# schematic.net
KiCad netlist of a schematic drawn in EasyEDA
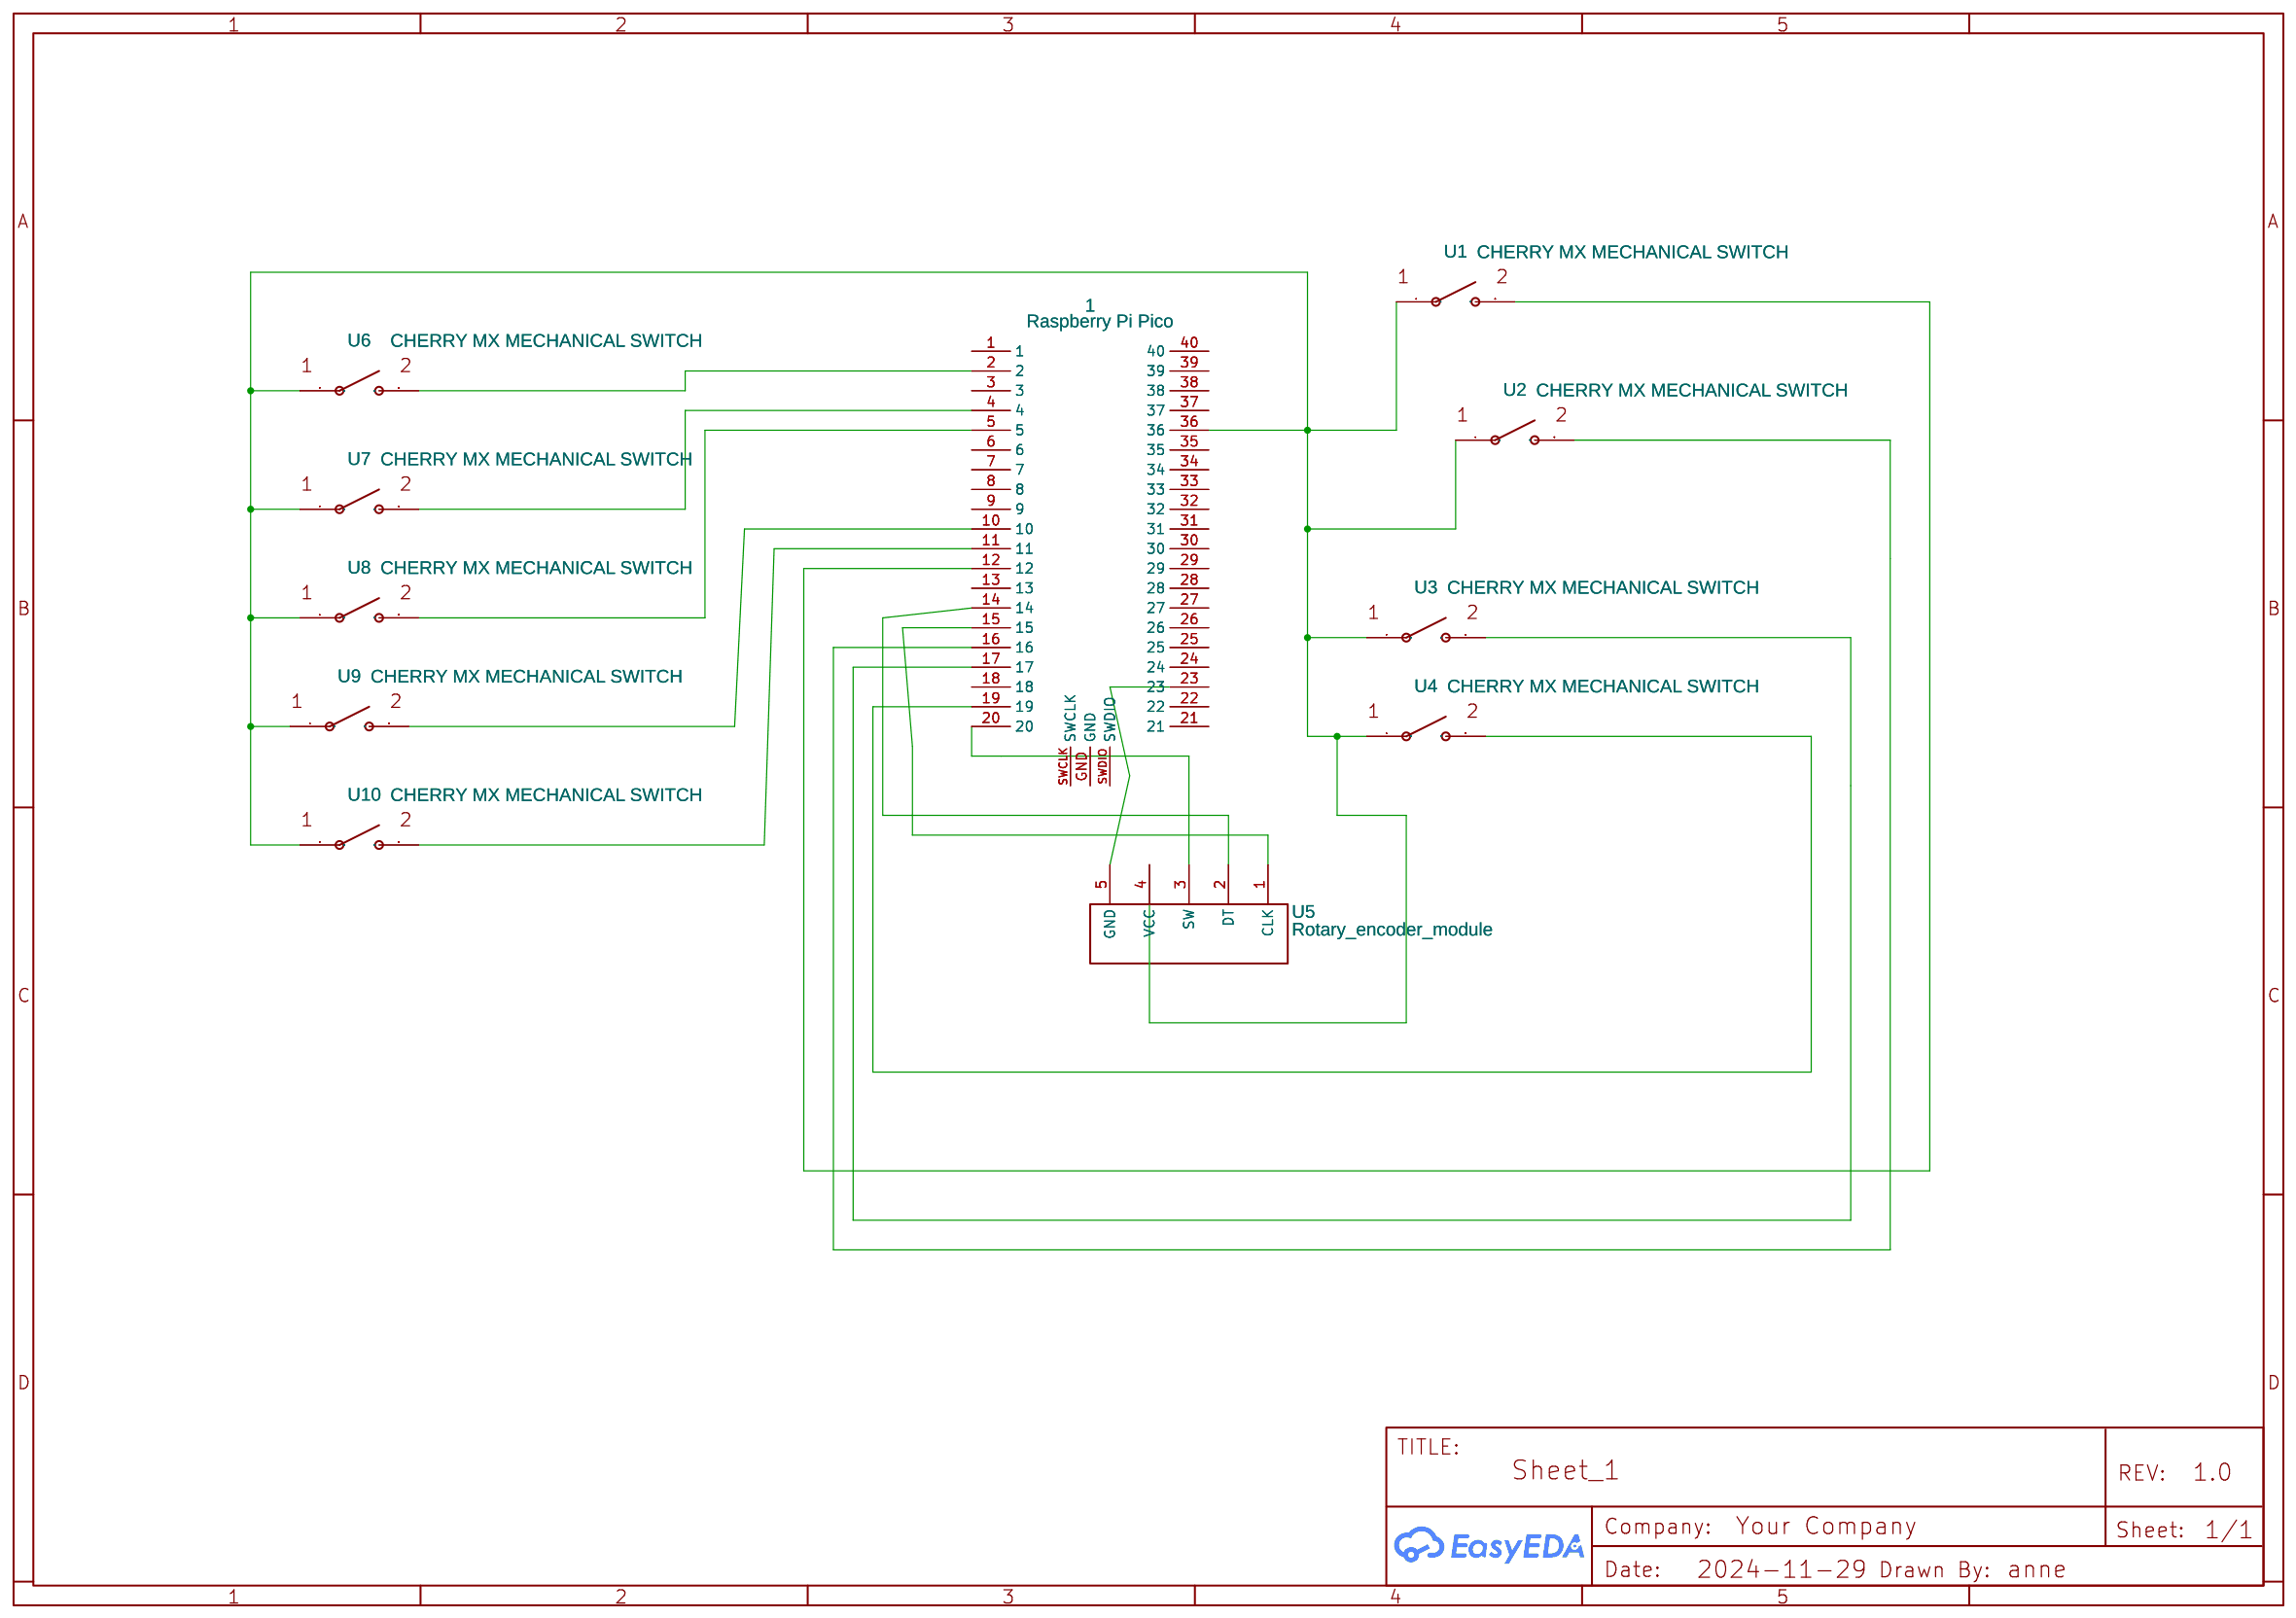
[diagram p0: schematic sheet]

(export (version "E")
  (design (tool "Eeschema 10.0.6"))
  (components
    (comp (ref "1") (value "Raspberry Pi Pico") (libsource (lib "") (part "Raspberry1")))
    (comp (ref "U1")
      (value "CHERRY MX MECHANICAL SWITCH")
      (libsource (lib "") (part "CHERRY MX MECHANICAL SWITCH"))
    )
    (comp (ref "U2")
      (value "CHERRY MX MECHANICAL SWITCH")
      (libsource (lib "") (part "CHERRY MX MECHANICAL SWITCH"))
    )
    (comp (ref "U3")
      (value "CHERRY MX MECHANICAL SWITCH")
      (libsource (lib "") (part "CHERRY MX MECHANICAL SWITCH"))
    )
    (comp (ref "U4")
      (value "CHERRY MX MECHANICAL SWITCH")
      (libsource (lib "") (part "CHERRY MX MECHANICAL SWITCH"))
    )
    (comp (ref "U5") (value "Rotary_encoder_module") (libsource (lib "") (part "Rotary_encoder_module")))
    (comp (ref "U6")
      (value "CHERRY MX MECHANICAL SWITCH")
      (libsource (lib "") (part "CHERRY MX MECHANICAL SWITCH"))
    )
    (comp (ref "U7")
      (value "CHERRY MX MECHANICAL SWITCH")
      (libsource (lib "") (part "CHERRY MX MECHANICAL SWITCH"))
    )
    (comp (ref "U8")
      (value "CHERRY MX MECHANICAL SWITCH")
      (libsource (lib "") (part "CHERRY MX MECHANICAL SWITCH"))
    )
    (comp (ref "U9")
      (value "CHERRY MX MECHANICAL SWITCH")
      (libsource (lib "") (part "CHERRY MX MECHANICAL SWITCH"))
    )
    (comp (ref "U10")
      (value "CHERRY MX MECHANICAL SWITCH")
      (libsource (lib "") (part "CHERRY MX MECHANICAL SWITCH"))
    )
  )
  (nets
    (net (code "1") (name "Net-(1-Pad2)") (class "Default")
      (node (ref "1") (pin "2") (pinfunction "2_2") (pintype "bidirectional"))
      (node (ref "U6") (pin "2") (pinfunction "2_2") (pintype "unspecified"))
    )
    (net (code "2") (name "Net-(1-Pad4)") (class "Default")
      (node (ref "1") (pin "4") (pinfunction "4_4") (pintype "bidirectional"))
      (node (ref "U7") (pin "2") (pinfunction "2_2") (pintype "unspecified"))
    )
    (net (code "3") (name "Net-(1-Pad5)") (class "Default")
      (node (ref "1") (pin "5") (pinfunction "5_5") (pintype "bidirectional"))
      (node (ref "U8") (pin "2") (pinfunction "2_2") (pintype "unspecified"))
    )
    (net (code "4") (name "Net-(1-Pad10)") (class "Default")
      (node (ref "1") (pin "10") (pinfunction "10_10") (pintype "bidirectional"))
      (node (ref "U9") (pin "2") (pinfunction "2_2") (pintype "unspecified"))
    )
    (net (code "5") (name "Net-(1-Pad11)") (class "Default")
      (node (ref "1") (pin "11") (pinfunction "11_11") (pintype "bidirectional"))
      (node (ref "U10") (pin "2") (pinfunction "2_2") (pintype "unspecified"))
    )
    (net (code "6") (name "Net-(1-Pad12)") (class "Default")
      (node (ref "1") (pin "12") (pinfunction "12_12") (pintype "bidirectional"))
      (node (ref "U1") (pin "2") (pinfunction "2_2") (pintype "unspecified"))
    )
    (net (code "7") (name "Net-(1-Pad16)") (class "Default")
      (node (ref "1") (pin "16") (pinfunction "16_16") (pintype "bidirectional"))
      (node (ref "U2") (pin "2") (pinfunction "2_2") (pintype "unspecified"))
    )
    (net (code "8") (name "Net-(1-Pad17)") (class "Default")
      (node (ref "1") (pin "17") (pinfunction "17_17") (pintype "bidirectional"))
      (node (ref "U3") (pin "2") (pinfunction "2_2") (pintype "unspecified"))
    )
    (net (code "9") (name "Net-(1-Pad19)") (class "Default")
      (node (ref "1") (pin "19") (pinfunction "19_19") (pintype "bidirectional"))
      (node (ref "U4") (pin "2") (pinfunction "2_2") (pintype "unspecified"))
    )
    (net (code "10") (name "Net-(U5-CLK)") (class "Default")
      (node (ref "1") (pin "15") (pinfunction "15_15") (pintype "bidirectional"))
      (node (ref "U5") (pin "1") (pinfunction "CLK_1") (pintype "unspecified"))
    )
    (net (code "11") (name "Net-(U5-DT)") (class "Default")
      (node (ref "1") (pin "14") (pinfunction "14_14") (pintype "bidirectional"))
      (node (ref "U5") (pin "2") (pinfunction "DT_2") (pintype "unspecified"))
    )
    (net (code "12") (name "Net-(U5-SW)") (class "Default")
      (node (ref "1") (pin "20") (pinfunction "20_20") (pintype "bidirectional"))
      (node (ref "U5") (pin "3") (pinfunction "SW_3") (pintype "unspecified"))
    )
    (net (code "13") (name "Net-(U5-VCC)") (class "Default")
      (node (ref "1") (pin "36") (pinfunction "36_36") (pintype "bidirectional"))
      (node (ref "U1") (pin "1") (pinfunction "1_1") (pintype "unspecified"))
      (node (ref "U10") (pin "1") (pinfunction "1_1") (pintype "unspecified"))
      (node (ref "U2") (pin "1") (pinfunction "1_1") (pintype "unspecified"))
      (node (ref "U3") (pin "1") (pinfunction "1_1") (pintype "unspecified"))
      (node (ref "U4") (pin "1") (pinfunction "1_1") (pintype "unspecified"))
      (node (ref "U5") (pin "4") (pinfunction "VCC_4") (pintype "unspecified"))
      (node (ref "U6") (pin "1") (pinfunction "1_1") (pintype "unspecified"))
      (node (ref "U7") (pin "1") (pinfunction "1_1") (pintype "unspecified"))
      (node (ref "U8") (pin "1") (pinfunction "1_1") (pintype "unspecified"))
      (node (ref "U9") (pin "1") (pinfunction "1_1") (pintype "unspecified"))
    )
    (net (code "14") (name "unconnected-(1-Pad1)") (class "Default")
      (node (ref "1") (pin "1") (pinfunction "1_1") (pintype "bidirectional"))
    )
    (net (code "15") (name "unconnected-(1-Pad3)") (class "Default")
      (node (ref "1") (pin "3") (pinfunction "3_3") (pintype "bidirectional"))
    )
    (net (code "16") (name "unconnected-(1-Pad6)") (class "Default")
      (node (ref "1") (pin "6") (pinfunction "6_6") (pintype "bidirectional"))
    )
    (net (code "17") (name "unconnected-(1-Pad7)") (class "Default")
      (node (ref "1") (pin "7") (pinfunction "7_7") (pintype "bidirectional"))
    )
    (net (code "18") (name "unconnected-(1-Pad8)") (class "Default")
      (node (ref "1") (pin "8") (pinfunction "8_8") (pintype "bidirectional"))
    )
    (net (code "19") (name "unconnected-(1-Pad9)") (class "Default")
      (node (ref "1") (pin "9") (pinfunction "9_9") (pintype "bidirectional"))
    )
    (net (code "20") (name "unconnected-(1-Pad13)") (class "Default")
      (node (ref "1") (pin "13") (pinfunction "13_13") (pintype "bidirectional"))
    )
    (net (code "21") (name "unconnected-(1-Pad18)") (class "Default")
      (node (ref "1") (pin "18") (pinfunction "18_18") (pintype "bidirectional"))
    )
    (net (code "22") (name "unconnected-(1-Pad21)") (class "Default")
      (node (ref "1") (pin "21") (pinfunction "21_21") (pintype "bidirectional"))
    )
    (net (code "23") (name "unconnected-(1-Pad22)") (class "Default")
      (node (ref "1") (pin "22") (pinfunction "22_22") (pintype "bidirectional"))
    )
    (net (code "24") (name "unconnected-(1-Pad23)") (class "Default")
      (node (ref "1") (pin "23") (pinfunction "23_23") (pintype "bidirectional"))
    )
    (net (code "25") (name "unconnected-(1-Pad24)") (class "Default")
      (node (ref "1") (pin "24") (pinfunction "24_24") (pintype "bidirectional"))
    )
    (net (code "26") (name "unconnected-(1-Pad25)") (class "Default")
      (node (ref "1") (pin "25") (pinfunction "25_25") (pintype "bidirectional"))
    )
    (net (code "27") (name "unconnected-(1-Pad26)") (class "Default")
      (node (ref "1") (pin "26") (pinfunction "26_26") (pintype "bidirectional"))
    )
    (net (code "28") (name "unconnected-(1-Pad27)") (class "Default")
      (node (ref "1") (pin "27") (pinfunction "27_27") (pintype "bidirectional"))
    )
    (net (code "29") (name "unconnected-(1-Pad28)") (class "Default")
      (node (ref "1") (pin "28") (pinfunction "28_28") (pintype "bidirectional"))
    )
    (net (code "30") (name "unconnected-(1-Pad29)") (class "Default")
      (node (ref "1") (pin "29") (pinfunction "29_29") (pintype "bidirectional"))
    )
    (net (code "31") (name "unconnected-(1-Pad30)") (class "Default")
      (node (ref "1") (pin "30") (pinfunction "30_30") (pintype "bidirectional"))
    )
    (net (code "32") (name "unconnected-(1-Pad31)") (class "Default")
      (node (ref "1") (pin "31") (pinfunction "31_31") (pintype "bidirectional"))
    )
    (net (code "33") (name "unconnected-(1-Pad32)") (class "Default")
      (node (ref "1") (pin "32") (pinfunction "32_32") (pintype "bidirectional"))
    )
    (net (code "34") (name "unconnected-(1-Pad33)") (class "Default")
      (node (ref "1") (pin "33") (pinfunction "33_33") (pintype "bidirectional"))
    )
    (net (code "35") (name "unconnected-(1-Pad34)") (class "Default")
      (node (ref "1") (pin "34") (pinfunction "34_34") (pintype "bidirectional"))
    )
    (net (code "36") (name "unconnected-(1-Pad35)") (class "Default")
      (node (ref "1") (pin "35") (pinfunction "35_35") (pintype "bidirectional"))
    )
    (net (code "37") (name "unconnected-(1-Pad37)") (class "Default")
      (node (ref "1") (pin "37") (pinfunction "37_37") (pintype "bidirectional"))
    )
    (net (code "38") (name "unconnected-(1-Pad38)") (class "Default")
      (node (ref "1") (pin "38") (pinfunction "38_38") (pintype "bidirectional"))
    )
    (net (code "39") (name "unconnected-(1-Pad39)") (class "Default")
      (node (ref "1") (pin "39") (pinfunction "39_39") (pintype "bidirectional"))
    )
    (net (code "40") (name "unconnected-(1-Pad40)") (class "Default")
      (node (ref "1") (pin "40") (pinfunction "40_40") (pintype "bidirectional"))
    )
    (net (code "41") (name "unconnected-(1-PadGND)") (class "Default")
      (node (ref "1") (pin "GND") (pinfunction "GND_GND") (pintype "bidirectional"))
    )
    (net (code "42") (name "unconnected-(1-PadSWCLK)") (class "Default")
      (node (ref "1") (pin "SWCLK") (pinfunction "SWCLK_SWCLK") (pintype "bidirectional"))
    )
    (net (code "43") (name "unconnected-(1-PadSWDIO)") (class "Default")
      (node (ref "1") (pin "SWDIO") (pinfunction "SWDIO_SWDIO") (pintype "bidirectional"))
    )
    (net (code "44") (name "unconnected-(U5-GND-Pad5)") (class "Default")
      (node (ref "U5") (pin "5") (pinfunction "GND_5") (pintype "unspecified"))
    )
  )
)
